# MCU_STM32H750VBT6.net
KiCad netlist of a schematic drawn in Altium Designer
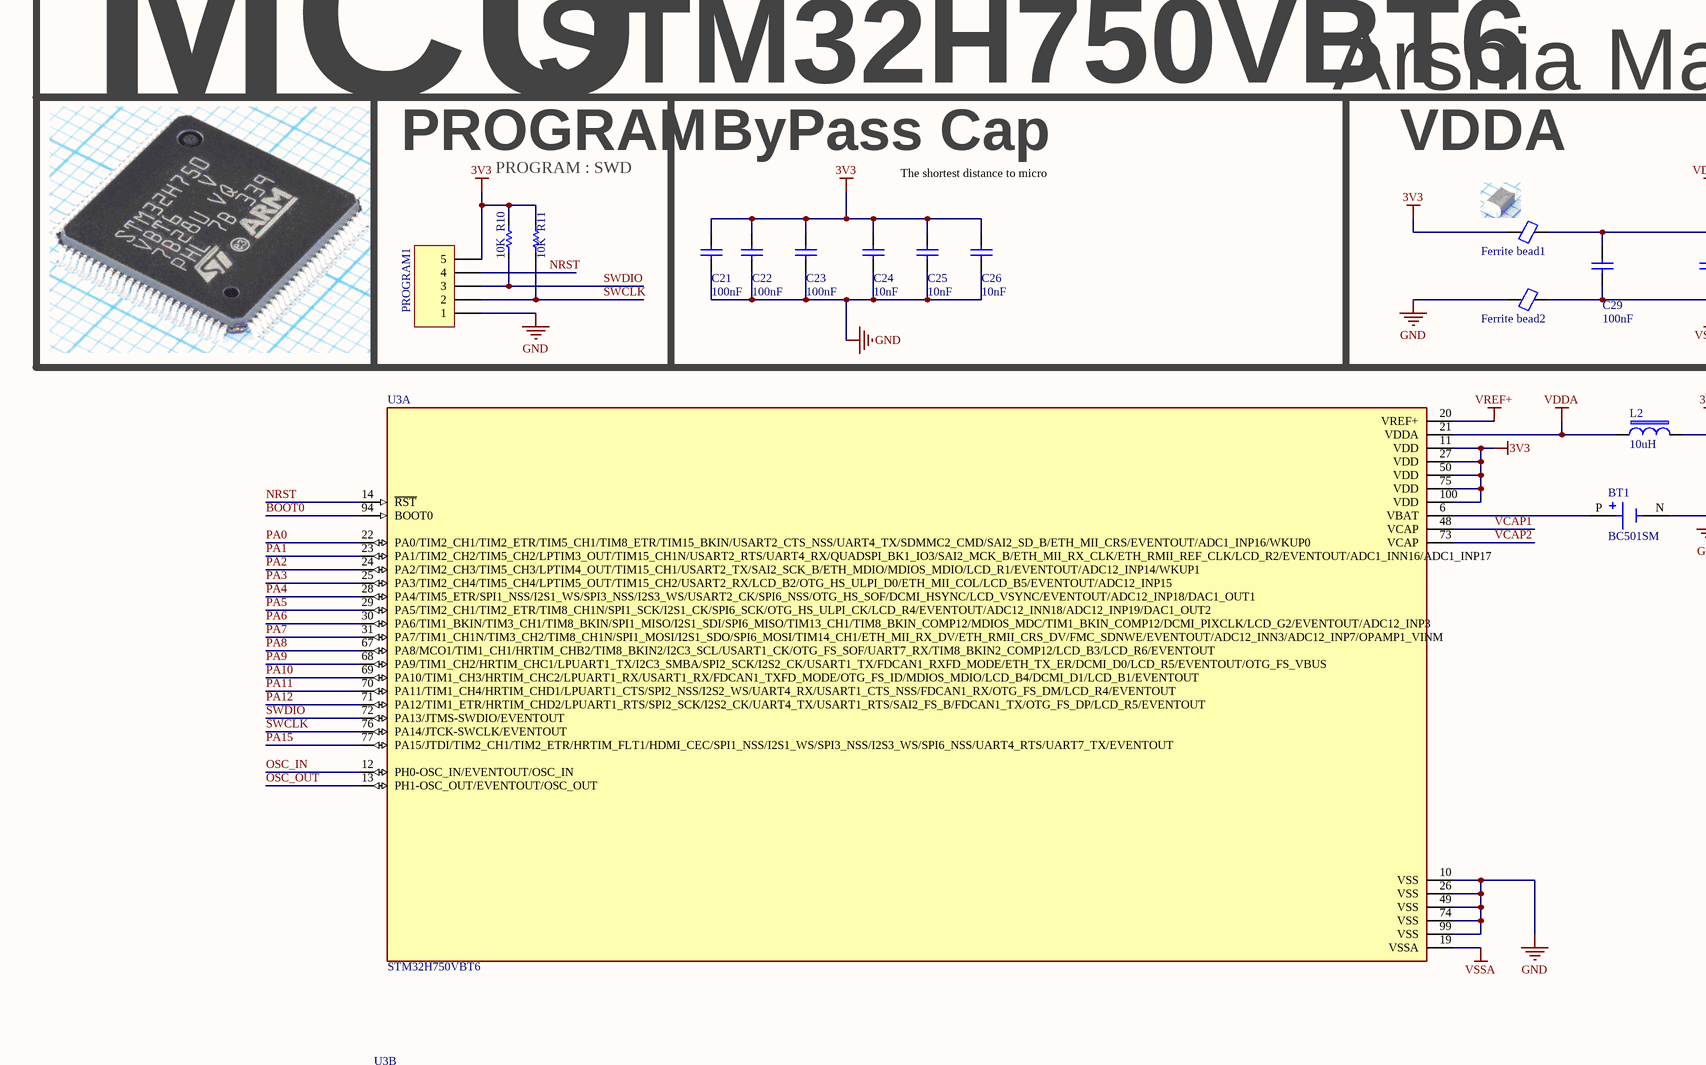
[diagram p0: MCU_STM32H750VBT6.SchDoc, top left]
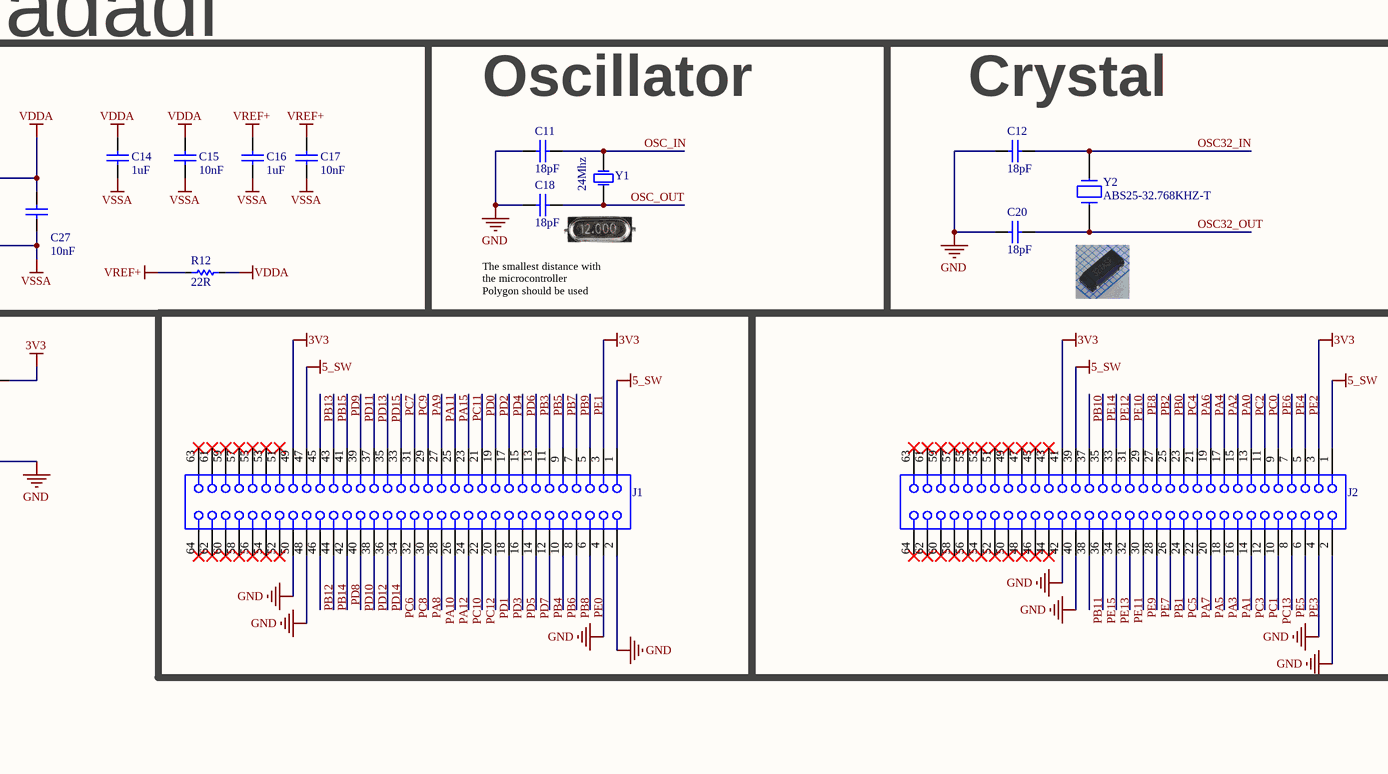
[diagram p1: MCU_STM32H750VBT6.SchDoc, top middle]
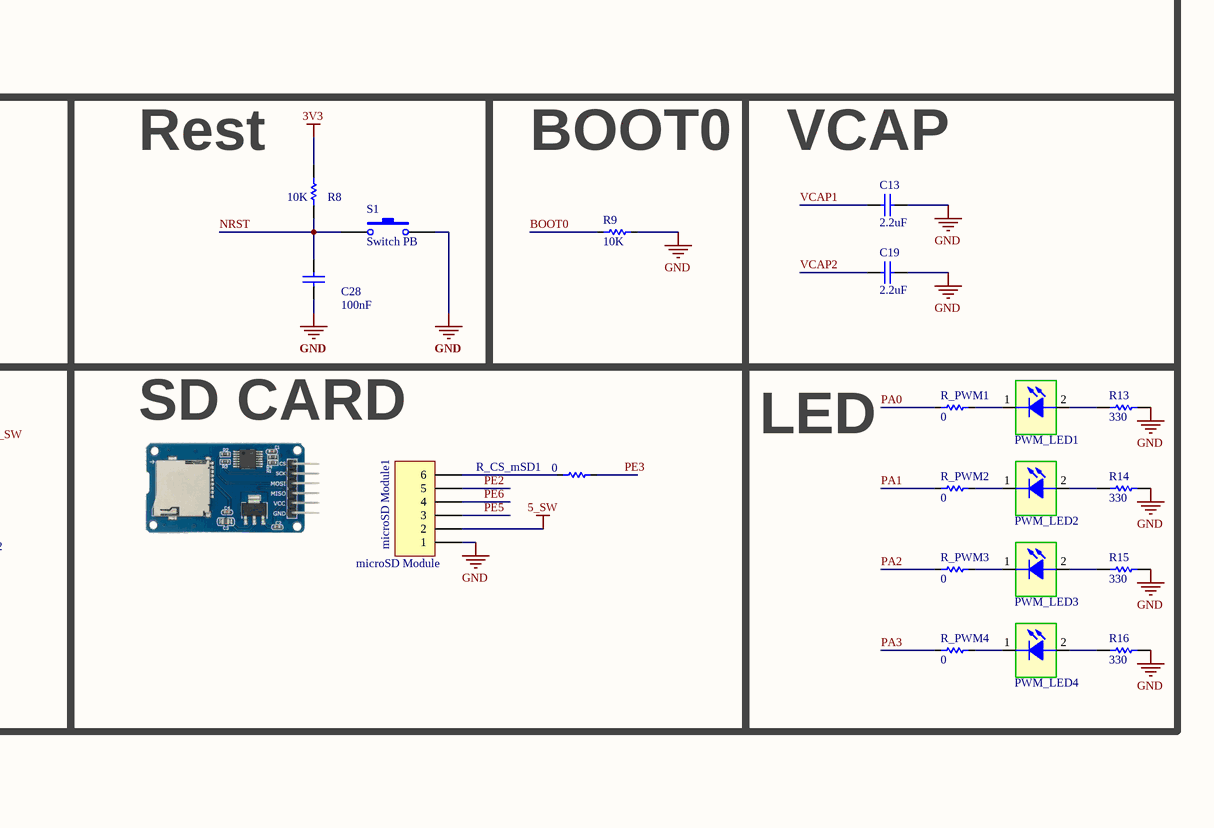
[diagram p2: MCU_STM32H750VBT6.SchDoc, top right]
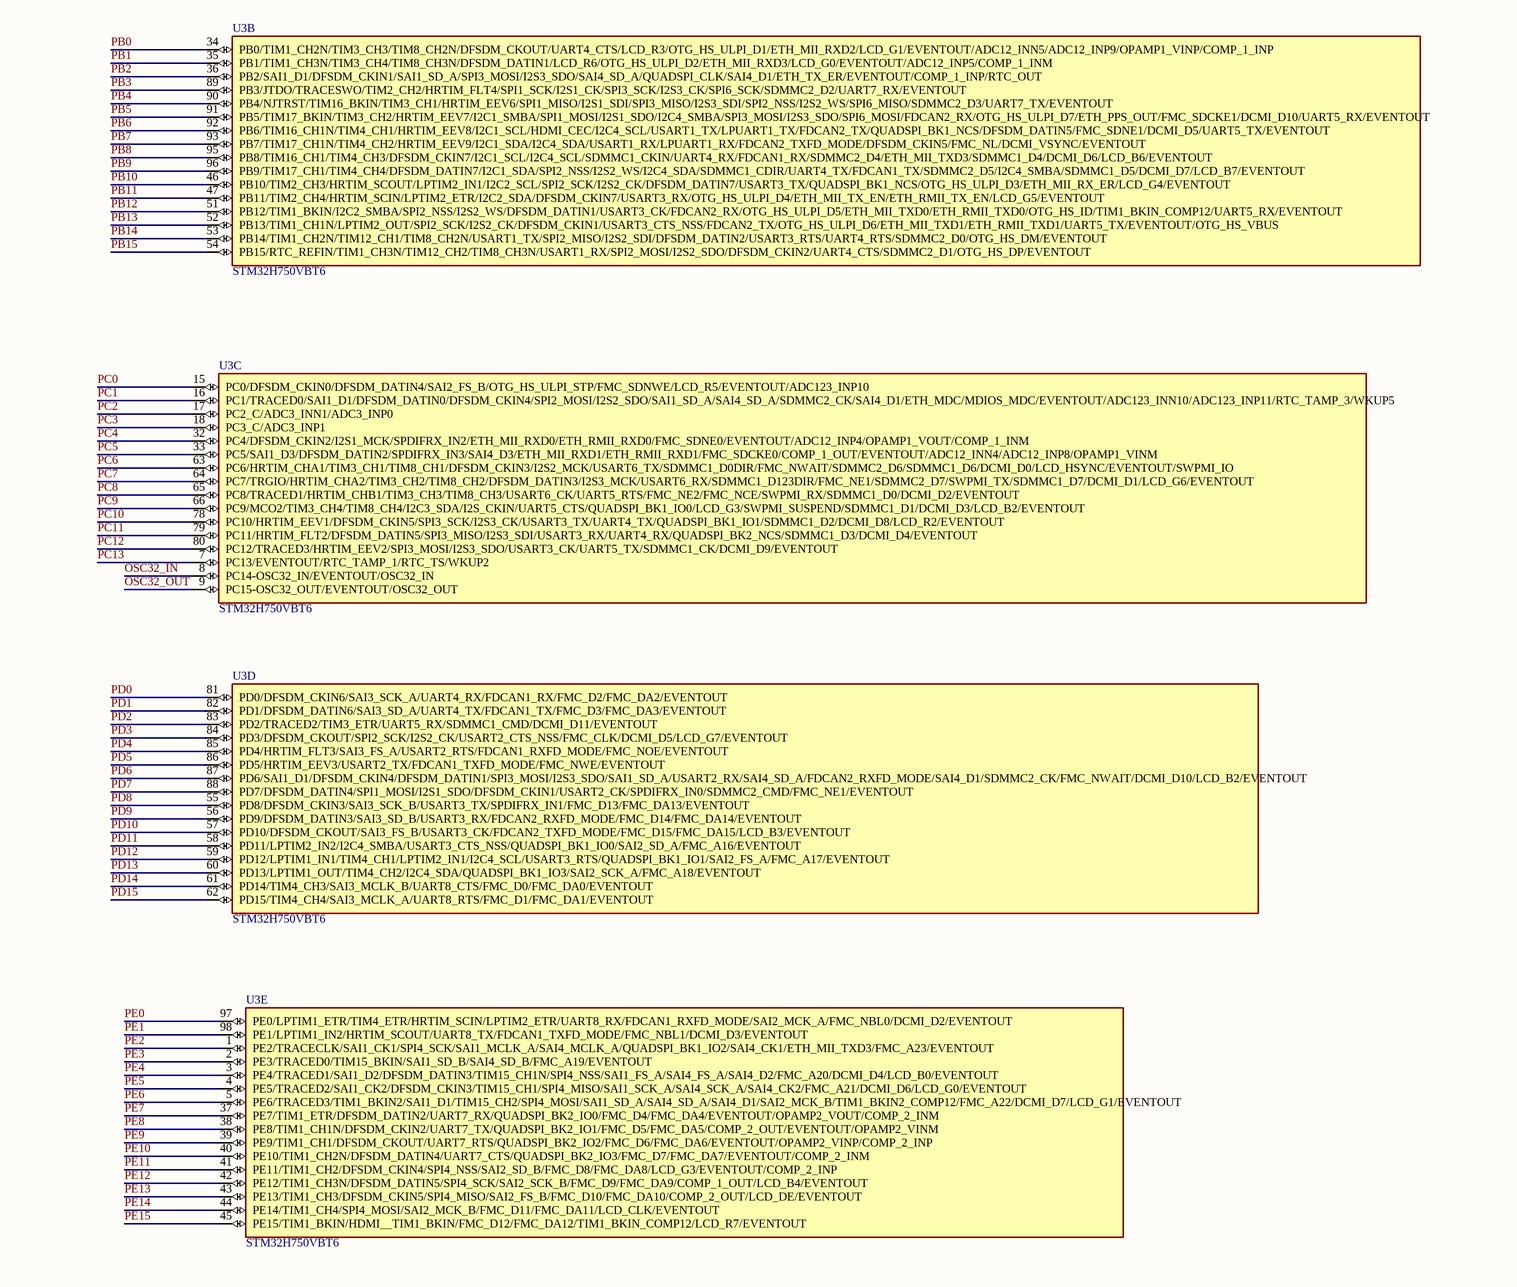
[diagram p3: MCU_STM32H750VBT6.SchDoc, bottom left]

(export (version "E")
  (design (tool "Eeschema 10.0.6"))
  (components
    (comp (ref "BT1")
      (value "BC501SM")
      (footprint "BAT_BC501SM")
      (description "BATTERY HOLDER COIN 12MM SMD")
      (fields (field (name "MF") "MPD"))
      (libsource (lib "BC501SM") (part "BC501SM"))
    )
    (comp (ref "C11")
      (value "18pF")
      (footprint "MY_CAP_SMD_0603")
      (description "CAP SMD_0603")
      (libsource (lib "AMINLIB") (part "CAP SMD_0603"))
    )
    (comp (ref "C12")
      (value "18pF")
      (footprint "MY_CAP_SMD_0603")
      (description "CAP SMD_0603")
      (libsource (lib "AMINLIB") (part "CAP SMD_0603"))
    )
    (comp (ref "C13")
      (value "2.2uF")
      (footprint "MY_CAP_SMD_0603")
      (description "CAP SMD_0603")
      (libsource (lib "AMINLIB") (part "CAP SMD_0603"))
    )
    (comp (ref "C14")
      (value "1uF")
      (footprint "MY_CAP_SMD_0603")
      (description "CAP SMD_0603")
      (libsource (lib "AMINLIB") (part "CAP SMD_0603"))
    )
    (comp (ref "C15")
      (value "10nF")
      (footprint "MY_CAP_SMD_0603")
      (description "CAP SMD_0603")
      (libsource (lib "AMINLIB") (part "CAP SMD_0603"))
    )
    (comp (ref "C16")
      (value "1uF")
      (footprint "MY_CAP_SMD_0603")
      (description "CAP SMD_0603")
      (libsource (lib "AMINLIB") (part "CAP SMD_0603"))
    )
    (comp (ref "C17")
      (value "10nF")
      (footprint "MY_CAP_SMD_0603")
      (description "CAP SMD_0603")
      (libsource (lib "AMINLIB") (part "CAP SMD_0603"))
    )
    (comp (ref "C18")
      (value "18pF")
      (footprint "MY_CAP_SMD_0603")
      (description "CAP SMD_0603")
      (libsource (lib "AMINLIB") (part "CAP SMD_0603"))
    )
    (comp (ref "C19")
      (value "2.2uF")
      (footprint "MY_CAP_SMD_0603")
      (description "CAP SMD_0603")
      (libsource (lib "AMINLIB") (part "CAP SMD_0603"))
    )
    (comp (ref "C20")
      (value "18pF")
      (footprint "MY_CAP_SMD_0603")
      (description "CAP SMD_0603")
      (libsource (lib "AMINLIB") (part "CAP SMD_0603"))
    )
    (comp (ref "C21")
      (value "100nF")
      (footprint "MY_CAP_SMD_0603")
      (description "CAP SMD_0603")
      (libsource (lib "AMINLIB") (part "CAP SMD_0603"))
    )
    (comp (ref "C22")
      (value "100nF")
      (footprint "MY_CAP_SMD_0603")
      (description "CAP SMD_0603")
      (libsource (lib "AMINLIB") (part "CAP SMD_0603"))
    )
    (comp (ref "C23")
      (value "100nF")
      (footprint "MY_CAP_SMD_0603")
      (description "CAP SMD_0603")
      (libsource (lib "AMINLIB") (part "CAP SMD_0603"))
    )
    (comp (ref "C24")
      (value "10nF")
      (footprint "MY_CAP_SMD_0603")
      (description "CAP SMD_0603")
      (libsource (lib "AMINLIB") (part "CAP SMD_0603"))
    )
    (comp (ref "C25")
      (value "10nF")
      (footprint "MY_CAP_SMD_0603")
      (description "CAP SMD_0603")
      (libsource (lib "AMINLIB") (part "CAP SMD_0603"))
    )
    (comp (ref "C26")
      (value "10nF")
      (footprint "MY_CAP_SMD_0603")
      (description "CAP SMD_0603")
      (libsource (lib "AMINLIB") (part "CAP SMD_0603"))
    )
    (comp (ref "C27")
      (value "10nF")
      (footprint "MY_CAP_SMD_0603")
      (description "CAP SMD_0603")
      (libsource (lib "AMINLIB") (part "CAP SMD_0603"))
    )
    (comp (ref "C28")
      (value "100nF")
      (footprint "MY_CAP_SMD_0603")
      (description "CAP SMD_0603")
      (libsource (lib "AMINLIB") (part "CAP SMD_0603"))
    )
    (comp (ref "C29")
      (value "100nF")
      (footprint "MY_CAP_SMD_0603")
      (description "CAP SMD_0603")
      (libsource (lib "AMINLIB") (part "CAP SMD_0603"))
    )
    (comp (ref "Ferrite bead1")
      (value "Ferrite Bead SMD")
      (footprint "FB1206")
      (fields (field (name "DESIGNER") "Ali Hafizi"))
      (libsource (lib "Altium") (part "Ferrite Bead SMD Package"))
    )
    (comp (ref "Ferrite bead2")
      (value "Ferrite Bead SMD")
      (footprint "FB1206")
      (fields (field (name "DESIGNER") "Ali Hafizi"))
      (libsource (lib "Altium") (part "Ferrite Bead SMD Package"))
    )
    (comp (ref "J1")
      (value "61306421821")
      (footprint "61306421821")
      (description "WR-PHD Socket Header, THT, Vertical, pitch 2.54mm, 2 Row, 64P")
      (fields (field (name "MANUFACTURER") "Wurth Elektronik"))
      (libsource (lib "Altium_WR-PHD_rev24a") (part "61306421821"))
    )
    (comp (ref "J2")
      (value "61306421821")
      (footprint "61306421821")
      (description "WR-PHD Socket Header, THT, Vertical, pitch 2.54mm, 2 Row, 64P")
      (fields (field (name "MANUFACTURER") "Wurth Elektronik"))
      (libsource (lib "Altium_WR-PHD_rev24a") (part "61306421821"))
    )
    (comp (ref "L2")
      (value "10uH")
      (footprint "10UH")
      (description "Inductor")
      (fields (field (name "PUBLISHER") "Altium Limited"))
      (libsource (lib "Sajad_Altium_Library") (part "Inductor_B"))
    )
    (comp (ref "microSD Module1")
      (value "microSD Module")
      (footprint "HDR1X6-1")
      (description "Header, 6-Pin")
      (fields (field (name "PUBLISHER") "Altium Limited"))
      (libsource (lib "Altium") (part "Header 6"))
    )
    (comp (ref "PROGRAM1")
      (value "Header 5")
      (footprint "My_1X05")
      (description "Header, 5-Pin")
      (fields (field (name "PUBLISHER") "Altium Limited"))
      (libsource (lib "AMINLIB") (part "Header 5"))
    )
    (comp (ref "PWM_LED1")
      (value "SMD 1206 LED")
      (footprint "LED 1206")
      (libsource (lib "Altium") (part "LED SMD 1206"))
    )
    (comp (ref "PWM_LED2")
      (value "SMD 1206 LED")
      (footprint "LED 1206")
      (libsource (lib "Altium") (part "LED SMD 1206"))
    )
    (comp (ref "PWM_LED3")
      (value "SMD 1206 LED")
      (footprint "LED 1206")
      (libsource (lib "Altium") (part "LED SMD 1206"))
    )
    (comp (ref "PWM_LED4")
      (value "SMD 1206 LED")
      (footprint "LED 1206")
      (libsource (lib "Altium") (part "LED SMD 1206"))
    )
    (comp (ref "R8")
      (value "10K")
      (footprint "RESC4817X04N")
      (description "RES 1206")
      (fields (field (name "DESIGNER") "Abbas Basereh"))
      (libsource (lib "Altium") (part "RES 1206 0.25W"))
    )
    (comp (ref "R9")
      (value "10K")
      (footprint "0805")
      (description "Resistor")
      (fields (field (name "PUBLISHER") "Altium Limited"))
      (libsource (lib "Sajad_Altium_Library") (part "Res"))
    )
    (comp (ref "R10")
      (value "10K")
      (footprint "0805")
      (description "Resistor")
      (fields (field (name "PUBLISHER") "Altium Limited"))
      (libsource (lib "Sajad_Altium_Library") (part "Res"))
    )
    (comp (ref "R11")
      (value "10K")
      (footprint "0805")
      (description "Resistor")
      (fields (field (name "PUBLISHER") "Altium Limited"))
      (libsource (lib "Sajad_Altium_Library") (part "Res"))
    )
    (comp (ref "R12")
      (value "22R")
      (footprint "0805")
      (description "Resistor")
      (fields (field (name "PUBLISHER") "Altium Limited"))
      (libsource (lib "Sajad_Altium_Library") (part "Res"))
    )
    (comp (ref "R13")
      (value "330")
      (footprint "RESC3413X04N")
      (description "RES 0805")
      (fields (field (name "DESIGNER") "Abbas Basereh"))
      (libsource (lib "Altium") (part "RES 0805 0.125W"))
    )
    (comp (ref "R14")
      (value "330")
      (footprint "RESC3413X04N")
      (description "RES 0805")
      (fields (field (name "DESIGNER") "Abbas Basereh"))
      (libsource (lib "Altium") (part "RES 0805 0.125W"))
    )
    (comp (ref "R15")
      (value "330")
      (footprint "RESC3413X04N")
      (description "RES 0805")
      (fields (field (name "DESIGNER") "Abbas Basereh"))
      (libsource (lib "Altium") (part "RES 0805 0.125W"))
    )
    (comp (ref "R16")
      (value "330")
      (footprint "RESC3413X04N")
      (description "RES 0805")
      (fields (field (name "DESIGNER") "Abbas Basereh"))
      (libsource (lib "Altium") (part "RES 0805 0.125W"))
    )
    (comp (ref "R_CS_mSD1")
      (value "0")
      (footprint "0805")
      (description "Resistor")
      (fields (field (name "PUBLISHER") "Altium Limited"))
      (libsource (lib "Sajad_Altium_Library") (part "Res"))
    )
    (comp (ref "R_PWM1")
      (value "0")
      (footprint "0805")
      (description "Resistor")
      (fields (field (name "PUBLISHER") "Altium Limited"))
      (libsource (lib "Sajad_Altium_Library") (part "Res"))
    )
    (comp (ref "R_PWM2")
      (value "0")
      (footprint "0805")
      (description "Resistor")
      (fields (field (name "PUBLISHER") "Altium Limited"))
      (libsource (lib "Sajad_Altium_Library") (part "Res"))
    )
    (comp (ref "R_PWM3")
      (value "0")
      (footprint "0805")
      (description "Resistor")
      (fields (field (name "PUBLISHER") "Altium Limited"))
      (libsource (lib "Sajad_Altium_Library") (part "Res"))
    )
    (comp (ref "R_PWM4")
      (value "0")
      (footprint "0805")
      (description "Resistor")
      (fields (field (name "PUBLISHER") "Altium Limited"))
      (libsource (lib "Sajad_Altium_Library") (part "Res"))
    )
    (comp (ref "S1")
      (value "Switch PB")
      (footprint "SW-PB")
      (description "Push Button Switch")
      (libsource (lib "my library") (part "Switch PB"))
    )
    (comp (ref "U3")
      (value "STM32H750VBT6")
      (footprint "QFP50P1600X1600X160-100N")
      (fields (field (name "MF") "STMicroelectronics"))
      (libsource (lib "STM32H750VBT6") (part "STM32H750VBT6"))
    )
    (comp (ref "Y1")
      (value "24Mhz")
      (footprint "Crystal")
      (description "Crystal Oscillator")
      (fields (field (name "PUBLISHER") "Altium Limited"))
      (libsource (lib "Sajad_Altium_Library") (part "XTAL"))
    )
    (comp (ref "Y2")
      (value "ABS25-32.768KHZ-T")
      (footprint "MY_CRYSTAL_SMD 6 X 3.3")
      (description "Crystal")
      (libsource (lib "AMINLIB") (part "CRYSTAL_SMD-6X3.3"))
    )
  )
  (nets
    (net (code "1") (name "/BOOT0") (class "Default")
      (node (ref "R9") (pin "1") (pinfunction "1_1") (pintype "passive"))
      (node (ref "U3") (pin "94") (pinfunction "BOOT0_94") (pintype "input"))
    )
    (net (code "2") (name "/NRST") (class "Default")
      (node (ref "C28") (pin "1") (pinfunction "1_1") (pintype "passive"))
      (node (ref "PROGRAM1") (pin "4") (pinfunction "4_4") (pintype "passive"))
      (node (ref "R8") (pin "1") (pinfunction "1_1") (pintype "passive"))
      (node (ref "S1") (pin "1") (pinfunction "1_1") (pintype "passive"))
      (node (ref "U3") (pin "14") (pinfunction "~{RST}_14") (pintype "input"))
    )
    (net (code "3") (name "/OSC32_IN") (class "Default")
      (node (ref "C12") (pin "2") (pinfunction "2_2") (pintype "passive"))
      (node (ref "U3") (pin "8") (pinfunction "PC14-OSC32_IN/EVENTOUT/OSC32_IN_8") (pintype "bidirectional"))
      (node (ref "Y2") (pin "4") (pinfunction "3_4") (pintype "passive"))
    )
    (net (code "4") (name "/OSC32_OUT") (class "Default")
      (node (ref "C20") (pin "2") (pinfunction "2_2") (pintype "passive"))
      (node (ref "U3") (pin "9") (pinfunction "PC15-OSC32_OUT/EVENTOUT/OSC32_OUT_9") (pintype "bidirectional"))
      (node (ref "Y2") (pin "2") (pinfunction "1_2") (pintype "passive"))
    )
    (net (code "5") (name "/OSC_IN") (class "Default")
      (node (ref "C11") (pin "2") (pinfunction "2_2") (pintype "passive"))
      (node (ref "U3") (pin "12") (pinfunction "PH0-OSC_IN/EVENTOUT/OSC_IN_12") (pintype "bidirectional"))
      (node (ref "Y1") (pin "2") (pinfunction "OSC2_2") (pintype "passive"))
    )
    (net (code "6") (name "/OSC_OUT") (class "Default")
      (node (ref "C18") (pin "2") (pinfunction "2_2") (pintype "passive"))
      (node (ref "U3") (pin "13") (pinfunction "PH1-OSC_OUT/EVENTOUT/OSC_OUT_13") (pintype "bidirectional"))
      (node (ref "Y1") (pin "1") (pinfunction "OSC1_1") (pintype "passive"))
    )
    (net (code "7") (name "/PA0") (class "Default")
      (node (ref "J2") (pin "15") (pinfunction "15_15") (pintype "passive"))
      (node (ref "R_PWM1") (pin "1") (pinfunction "1_1") (pintype "passive"))
      (node (ref "U3") (pin "22") (pinfunction "PA0/TIM2_CH1/TIM2_ETR/TIM5_CH1/TIM8_ETR/TIM15_BKIN/USART2_CTS_NSS/UART4_TX/SDMMC2_CMD/SAI2_SD_B/ETH_MII_CRS/EVENTOUT/ADC1_INP16/WKUP0_22") (pintype "bidirectional"))
    )
    (net (code "8") (name "/PA1") (class "Default")
      (node (ref "J2") (pin "16") (pinfunction "16_16") (pintype "passive"))
      (node (ref "R_PWM2") (pin "1") (pinfunction "1_1") (pintype "passive"))
      (node (ref "U3") (pin "23") (pinfunction "PA1/TIM2_CH2/TIM5_CH2/LPTIM3_OUT/TIM15_CH1N/USART2_RTS/UART4_RX/QUADSPI_BK1_IO3/SAI2_MCK_B/ETH_MII_RX_CLK/ETH_RMII_REF_CLK/LCD_R2/EVENTOUT/ADC1_INN16/ADC1_INP17_23") (pintype "bidirectional"))
    )
    (net (code "9") (name "/PA2") (class "Default")
      (node (ref "J2") (pin "17") (pinfunction "17_17") (pintype "passive"))
      (node (ref "R_PWM3") (pin "1") (pinfunction "1_1") (pintype "passive"))
      (node (ref "U3") (pin "24") (pinfunction "PA2/TIM2_CH3/TIM5_CH3/LPTIM4_OUT/TIM15_CH1/USART2_TX/SAI2_SCK_B/ETH_MDIO/MDIOS_MDIO/LCD_R1/EVENTOUT/ADC12_INP14/WKUP1_24") (pintype "bidirectional"))
    )
    (net (code "10") (name "/PA3") (class "Default")
      (node (ref "J2") (pin "18") (pinfunction "18_18") (pintype "passive"))
      (node (ref "R_PWM4") (pin "1") (pinfunction "1_1") (pintype "passive"))
      (node (ref "U3") (pin "25") (pinfunction "PA3/TIM2_CH4/TIM5_CH4/LPTIM5_OUT/TIM15_CH2/USART2_RX/LCD_B2/OTG_HS_ULPI_D0/ETH_MII_COL/LCD_B5/EVENTOUT/ADC12_INP15_25") (pintype "bidirectional"))
    )
    (net (code "11") (name "/PA4") (class "Default")
      (node (ref "J2") (pin "19") (pinfunction "19_19") (pintype "passive"))
      (node (ref "U3") (pin "28") (pinfunction "PA4/TIM5_ETR/SPI1_NSS/I2S1_WS/SPI3_NSS/I2S3_WS/USART2_CK/SPI6_NSS/OTG_HS_SOF/DCMI_HSYNC/LCD_VSYNC/EVENTOUT/ADC12_INP18/DAC1_OUT1_28") (pintype "bidirectional"))
    )
    (net (code "12") (name "/PA5") (class "Default")
      (node (ref "J2") (pin "20") (pinfunction "20_20") (pintype "passive"))
      (node (ref "U3") (pin "29") (pinfunction "PA5/TIM2_CH1/TIM2_ETR/TIM8_CH1N/SPI1_SCK/I2S1_CK/SPI6_SCK/OTG_HS_ULPI_CK/LCD_R4/EVENTOUT/ADC12_INN18/ADC12_INP19/DAC1_OUT2_29") (pintype "bidirectional"))
    )
    (net (code "13") (name "/PA6") (class "Default")
      (node (ref "J2") (pin "21") (pinfunction "21_21") (pintype "passive"))
      (node (ref "U3") (pin "30") (pinfunction "PA6/TIM1_BKIN/TIM3_CH1/TIM8_BKIN/SPI1_MISO/I2S1_SDI/SPI6_MISO/TIM13_CH1/TIM8_BKIN_COMP12/MDIOS_MDC/TIM1_BKIN_COMP12/DCMI_PIXCLK/LCD_G2/EVENTOUT/ADC12_INP3_30") (pintype "bidirectional"))
    )
    (net (code "14") (name "/PA7") (class "Default")
      (node (ref "J2") (pin "22") (pinfunction "22_22") (pintype "passive"))
      (node (ref "U3") (pin "31") (pinfunction "PA7/TIM1_CH1N/TIM3_CH2/TIM8_CH1N/SPI1_MOSI/I2S1_SDO/SPI6_MOSI/TIM14_CH1/ETH_MII_RX_DV/ETH_RMII_CRS_DV/FMC_SDNWE/EVENTOUT/ADC12_INN3/ADC12_INP7/OPAMP1_VINM_31") (pintype "bidirectional"))
    )
    (net (code "15") (name "/PA8") (class "Default")
      (node (ref "J1") (pin "30") (pinfunction "30_30") (pintype "passive"))
      (node (ref "U3") (pin "67") (pinfunction "PA8/MCO1/TIM1_CH1/HRTIM_CHB2/TIM8_BKIN2/I2C3_SCL/USART1_CK/OTG_FS_SOF/UART7_RX/TIM8_BKIN2_COMP12/LCD_B3/LCD_R6/EVENTOUT_67") (pintype "bidirectional"))
    )
    (net (code "16") (name "/PA9") (class "Default")
      (node (ref "J1") (pin "29") (pinfunction "29_29") (pintype "passive"))
      (node (ref "U3") (pin "68") (pinfunction "PA9/TIM1_CH2/HRTIM_CHC1/LPUART1_TX/I2C3_SMBA/SPI2_SCK/I2S2_CK/USART1_TX/FDCAN1_RXFD_MODE/ETH_TX_ER/DCMI_D0/LCD_R5/EVENTOUT/OTG_FS_VBUS_68") (pintype "bidirectional"))
    )
    (net (code "17") (name "/PA10") (class "Default")
      (node (ref "J1") (pin "28") (pinfunction "28_28") (pintype "passive"))
      (node (ref "U3") (pin "69") (pinfunction "PA10/TIM1_CH3/HRTIM_CHC2/LPUART1_RX/USART1_RX/FDCAN1_TXFD_MODE/OTG_FS_ID/MDIOS_MDIO/LCD_B4/DCMI_D1/LCD_B1/EVENTOUT_69") (pintype "bidirectional"))
    )
    (net (code "18") (name "/PA11") (class "Default")
      (node (ref "J1") (pin "27") (pinfunction "27_27") (pintype "passive"))
      (node (ref "U3") (pin "70") (pinfunction "PA11/TIM1_CH4/HRTIM_CHD1/LPUART1_CTS/SPI2_NSS/I2S2_WS/UART4_RX/USART1_CTS_NSS/FDCAN1_RX/OTG_FS_DM/LCD_R4/EVENTOUT_70") (pintype "bidirectional"))
    )
    (net (code "19") (name "/PA12") (class "Default")
      (node (ref "J1") (pin "26") (pinfunction "26_26") (pintype "passive"))
      (node (ref "U3") (pin "71") (pinfunction "PA12/TIM1_ETR/HRTIM_CHD2/LPUART1_RTS/SPI2_SCK/I2S2_CK/UART4_TX/USART1_RTS/SAI2_FS_B/FDCAN1_TX/OTG_FS_DP/LCD_R5/EVENTOUT_71") (pintype "bidirectional"))
    )
    (net (code "20") (name "/PA15") (class "Default")
      (node (ref "J1") (pin "25") (pinfunction "25_25") (pintype "passive"))
      (node (ref "U3") (pin "77") (pinfunction "PA15/JTDI/TIM2_CH1/TIM2_ETR/HRTIM_FLT1/HDMI_CEC/SPI1_NSS/I2S1_WS/SPI3_NSS/I2S3_WS/SPI6_NSS/UART4_RTS/UART7_TX/EVENTOUT_77") (pintype "bidirectional"))
    )
    (net (code "21") (name "/PB0") (class "Default")
      (node (ref "J2") (pin "25") (pinfunction "25_25") (pintype "passive"))
      (node (ref "U3") (pin "34") (pinfunction "PB0/TIM1_CH2N/TIM3_CH3/TIM8_CH2N/DFSDM_CKOUT/UART4_CTS/LCD_R3/OTG_HS_ULPI_D1/ETH_MII_RXD2/LCD_G1/EVENTOUT/ADC12_INN5/ADC12_INP9/OPAMP1_VINP/COMP_1_INP_34") (pintype "bidirectional"))
    )
    (net (code "22") (name "/PB1") (class "Default")
      (node (ref "J2") (pin "26") (pinfunction "26_26") (pintype "passive"))
      (node (ref "U3") (pin "35") (pinfunction "PB1/TIM1_CH3N/TIM3_CH4/TIM8_CH3N/DFSDM_DATIN1/LCD_R6/OTG_HS_ULPI_D2/ETH_MII_RXD3/LCD_G0/EVENTOUT/ADC12_INP5/COMP_1_INM_35") (pintype "bidirectional"))
    )
    (net (code "23") (name "/PB2") (class "Default")
      (node (ref "J2") (pin "27") (pinfunction "27_27") (pintype "passive"))
      (node (ref "U3") (pin "36") (pinfunction "PB2/SAI1_D1/DFSDM_CKIN1/SAI1_SD_A/SPI3_MOSI/I2S3_SDO/SAI4_SD_A/QUADSPI_CLK/SAI4_D1/ETH_TX_ER/EVENTOUT/COMP_1_INP/RTC_OUT_36") (pintype "bidirectional"))
    )
    (net (code "24") (name "/PB3") (class "Default")
      (node (ref "J1") (pin "13") (pinfunction "13_13") (pintype "passive"))
      (node (ref "U3") (pin "89") (pinfunction "PB3/JTDO/TRACESWO/TIM2_CH2/HRTIM_FLT4/SPI1_SCK/I2S1_CK/SPI3_SCK/I2S3_CK/SPI6_SCK/SDMMC2_D2/UART7_RX/EVENTOUT_89") (pintype "bidirectional"))
    )
    (net (code "25") (name "/PB4") (class "Default")
      (node (ref "J1") (pin "12") (pinfunction "12_12") (pintype "passive"))
      (node (ref "U3") (pin "90") (pinfunction "PB4/NJTRST/TIM16_BKIN/TIM3_CH1/HRTIM_EEV6/SPI1_MISO/I2S1_SDI/SPI3_MISO/I2S3_SDI/SPI2_NSS/I2S2_WS/SPI6_MISO/SDMMC2_D3/UART7_TX/EVENTOUT_90") (pintype "bidirectional"))
    )
    (net (code "26") (name "/PB5") (class "Default")
      (node (ref "J1") (pin "11") (pinfunction "11_11") (pintype "passive"))
      (node (ref "U3") (pin "91") (pinfunction "PB5/TIM17_BKIN/TIM3_CH2/HRTIM_EEV7/I2C1_SMBA/SPI1_MOSI/I2S1_SDO/I2C4_SMBA/SPI3_MOSI/I2S3_SDO/SPI6_MOSI/FDCAN2_RX/OTG_HS_ULPI_D7/ETH_PPS_OUT/FMC_SDCKE1/DCMI_D10/UART5_RX/EVENTOUT_91") (pintype "bidirectional"))
    )
    (net (code "27") (name "/PB6") (class "Default")
      (node (ref "J1") (pin "10") (pinfunction "10_10") (pintype "passive"))
      (node (ref "U3") (pin "92") (pinfunction "PB6/TIM16_CH1N/TIM4_CH1/HRTIM_EEV8/I2C1_SCL/HDMI_CEC/I2C4_SCL/USART1_TX/LPUART1_TX/FDCAN2_TX/QUADSPI_BK1_NCS/DFSDM_DATIN5/FMC_SDNE1/DCMI_D5/UART5_TX/EVENTOUT_92") (pintype "bidirectional"))
    )
    (net (code "28") (name "/PB7") (class "Default")
      (node (ref "J1") (pin "9") (pinfunction "9_9") (pintype "passive"))
      (node (ref "U3") (pin "93") (pinfunction "PB7/TIM17_CH1N/TIM4_CH2/HRTIM_EEV9/I2C1_SDA/I2C4_SDA/USART1_RX/LPUART1_RX/FDCAN2_TXFD_MODE/DFSDM_CKIN5/FMC_NL/DCMI_VSYNC/EVENTOUT_93") (pintype "bidirectional"))
    )
    (net (code "29") (name "/PB8") (class "Default")
      (node (ref "J1") (pin "8") (pinfunction "8_8") (pintype "passive"))
      (node (ref "U3") (pin "95") (pinfunction "PB8/TIM16_CH1/TIM4_CH3/DFSDM_CKIN7/I2C1_SCL/I2C4_SCL/SDMMC1_CKIN/UART4_RX/FDCAN1_RX/SDMMC2_D4/ETH_MII_TXD3/SDMMC1_D4/DCMI_D6/LCD_B6/EVENTOUT_95") (pintype "bidirectional"))
    )
    (net (code "30") (name "/PB9") (class "Default")
      (node (ref "J1") (pin "7") (pinfunction "7_7") (pintype "passive"))
      (node (ref "U3") (pin "96") (pinfunction "PB9/TIM17_CH1/TIM4_CH4/DFSDM_DATIN7/I2C1_SDA/SPI2_NSS/I2S2_WS/I2C4_SDA/SDMMC1_CDIR/UART4_TX/FDCAN1_TX/SDMMC2_D5/I2C4_SMBA/SDMMC1_D5/DCMI_D7/LCD_B7/EVENTOUT_96") (pintype "bidirectional"))
    )
    (net (code "31") (name "/PB10") (class "Default")
      (node (ref "J2") (pin "37") (pinfunction "37_37") (pintype "passive"))
      (node (ref "U3") (pin "46") (pinfunction "PB10/TIM2_CH3/HRTIM_SCOUT/LPTIM2_IN1/I2C2_SCL/SPI2_SCK/I2S2_CK/DFSDM_DATIN7/USART3_TX/QUADSPI_BK1_NCS/OTG_HS_ULPI_D3/ETH_MII_RX_ER/LCD_G4/EVENTOUT_46") (pintype "bidirectional"))
    )
    (net (code "32") (name "/PB11") (class "Default")
      (node (ref "J2") (pin "38") (pinfunction "38_38") (pintype "passive"))
      (node (ref "U3") (pin "47") (pinfunction "PB11/TIM2_CH4/HRTIM_SCIN/LPTIM2_ETR/I2C2_SDA/DFSDM_CKIN7/USART3_RX/OTG_HS_ULPI_D4/ETH_MII_TX_EN/ETH_RMII_TX_EN/LCD_G5/EVENTOUT_47") (pintype "bidirectional"))
    )
    (net (code "33") (name "/PB12") (class "Default")
      (node (ref "J1") (pin "46") (pinfunction "46_46") (pintype "passive"))
      (node (ref "U3") (pin "51") (pinfunction "PB12/TIM1_BKIN/I2C2_SMBA/SPI2_NSS/I2S2_WS/DFSDM_DATIN1/USART3_CK/FDCAN2_RX/OTG_HS_ULPI_D5/ETH_MII_TXD0/ETH_RMII_TXD0/OTG_HS_ID/TIM1_BKIN_COMP12/UART5_RX/EVENTOUT_51") (pintype "bidirectional"))
    )
    (net (code "34") (name "/PB13") (class "Default")
      (node (ref "J1") (pin "45") (pinfunction "45_45") (pintype "passive"))
      (node (ref "U3") (pin "52") (pinfunction "PB13/TIM1_CH1N/LPTIM2_OUT/SPI2_SCK/I2S2_CK/DFSDM_CKIN1/USART3_CTS_NSS/FDCAN2_TX/OTG_HS_ULPI_D6/ETH_MII_TXD1/ETH_RMII_TXD1/UART5_TX/EVENTOUT/OTG_HS_VBUS_52") (pintype "bidirectional"))
    )
    (net (code "35") (name "/PB14") (class "Default")
      (node (ref "J1") (pin "44") (pinfunction "44_44") (pintype "passive"))
      (node (ref "U3") (pin "53") (pinfunction "PB14/TIM1_CH2N/TIM12_CH1/TIM8_CH2N/USART1_TX/SPI2_MISO/I2S2_SDI/DFSDM_DATIN2/USART3_RTS/UART4_RTS/SDMMC2_D0/OTG_HS_DM/EVENTOUT_53") (pintype "bidirectional"))
    )
    (net (code "36") (name "/PB15") (class "Default")
      (node (ref "J1") (pin "43") (pinfunction "43_43") (pintype "passive"))
      (node (ref "U3") (pin "54") (pinfunction "PB15/RTC_REFIN/TIM1_CH3N/TIM12_CH2/TIM8_CH3N/USART1_RX/SPI2_MOSI/I2S2_SDO/DFSDM_CKIN2/UART4_CTS/SDMMC2_D1/OTG_HS_DP/EVENTOUT_54") (pintype "bidirectional"))
    )
    (net (code "37") (name "/PC0") (class "Default")
      (node (ref "J2") (pin "11") (pinfunction "11_11") (pintype "passive"))
      (node (ref "U3") (pin "15") (pinfunction "PC0/DFSDM_CKIN0/DFSDM_DATIN4/SAI2_FS_B/OTG_HS_ULPI_STP/FMC_SDNWE/LCD_R5/EVENTOUT/ADC123_INP10_15") (pintype "bidirectional"))
    )
    (net (code "38") (name "/PC1") (class "Default")
      (node (ref "J2") (pin "12") (pinfunction "12_12") (pintype "passive"))
      (node (ref "U3") (pin "16") (pinfunction "PC1/TRACED0/SAI1_D1/DFSDM_DATIN0/DFSDM_CKIN4/SPI2_MOSI/I2S2_SDO/SAI1_SD_A/SAI4_SD_A/SDMMC2_CK/SAI4_D1/ETH_MDC/MDIOS_MDC/EVENTOUT/ADC123_INN10/ADC123_INP11/RTC_TAMP_3/WKUP5_16") (pintype "bidirectional"))
    )
    (net (code "39") (name "/PC2") (class "Default")
      (node (ref "J2") (pin "13") (pinfunction "13_13") (pintype "passive"))
      (node (ref "U3") (pin "17") (pinfunction "PC2_C/ADC3_INN1/ADC3_INP0_17") (pintype "bidirectional"))
    )
    (net (code "40") (name "/PC3") (class "Default")
      (node (ref "J2") (pin "14") (pinfunction "14_14") (pintype "passive"))
      (node (ref "U3") (pin "18") (pinfunction "PC3_C/ADC3_INP1_18") (pintype "bidirectional"))
    )
    (net (code "41") (name "/PC4") (class "Default")
      (node (ref "J2") (pin "23") (pinfunction "23_23") (pintype "passive"))
      (node (ref "U3") (pin "32") (pinfunction "PC4/DFSDM_CKIN2/I2S1_MCK/SPDIFRX_IN2/ETH_MII_RXD0/ETH_RMII_RXD0/FMC_SDNE0/EVENTOUT/ADC12_INP4/OPAMP1_VOUT/COMP_1_INM_32") (pintype "bidirectional"))
    )
    (net (code "42") (name "/PC5") (class "Default")
      (node (ref "J2") (pin "24") (pinfunction "24_24") (pintype "passive"))
      (node (ref "U3") (pin "33") (pinfunction "PC5/SAI1_D3/DFSDM_DATIN2/SPDIFRX_IN3/SAI4_D3/ETH_MII_RXD1/ETH_RMII_RXD1/FMC_SDCKE0/COMP_1_OUT/EVENTOUT/ADC12_INN4/ADC12_INP8/OPAMP1_VINM_33") (pintype "bidirectional"))
    )
    (net (code "43") (name "/PC6") (class "Default")
      (node (ref "J1") (pin "34") (pinfunction "34_34") (pintype "passive"))
      (node (ref "U3") (pin "63") (pinfunction "PC6/HRTIM_CHA1/TIM3_CH1/TIM8_CH1/DFSDM_CKIN3/I2S2_MCK/USART6_TX/SDMMC1_D0DIR/FMC_NWAIT/SDMMC2_D6/SDMMC1_D6/DCMI_D0/LCD_HSYNC/EVENTOUT/SWPMI_IO_63") (pintype "bidirectional"))
    )
    (net (code "44") (name "/PC7") (class "Default")
      (node (ref "J1") (pin "33") (pinfunction "33_33") (pintype "passive"))
      (node (ref "U3") (pin "64") (pinfunction "PC7/TRGIO/HRTIM_CHA2/TIM3_CH2/TIM8_CH2/DFSDM_DATIN3/I2S3_MCK/USART6_RX/SDMMC1_D123DIR/FMC_NE1/SDMMC2_D7/SWPMI_TX/SDMMC1_D7/DCMI_D1/LCD_G6/EVENTOUT_64") (pintype "bidirectional"))
    )
    (net (code "45") (name "/PC8") (class "Default")
      (node (ref "J1") (pin "32") (pinfunction "32_32") (pintype "passive"))
      (node (ref "U3") (pin "65") (pinfunction "PC8/TRACED1/HRTIM_CHB1/TIM3_CH3/TIM8_CH3/USART6_CK/UART5_RTS/FMC_NE2/FMC_NCE/SWPMI_RX/SDMMC1_D0/DCMI_D2/EVENTOUT_65") (pintype "bidirectional"))
    )
    (net (code "46") (name "/PC9") (class "Default")
      (node (ref "J1") (pin "31") (pinfunction "31_31") (pintype "passive"))
      (node (ref "U3") (pin "66") (pinfunction "PC9/MCO2/TIM3_CH4/TIM8_CH4/I2C3_SDA/I2S_CKIN/UART5_CTS/QUADSPI_BK1_IO0/LCD_G3/SWPMI_SUSPEND/SDMMC1_D1/DCMI_D3/LCD_B2/EVENTOUT_66") (pintype "bidirectional"))
    )
    (net (code "47") (name "/PC10") (class "Default")
      (node (ref "J1") (pin "24") (pinfunction "24_24") (pintype "passive"))
      (node (ref "U3") (pin "78") (pinfunction "PC10/HRTIM_EEV1/DFSDM_CKIN5/SPI3_SCK/I2S3_CK/USART3_TX/UART4_TX/QUADSPI_BK1_IO1/SDMMC1_D2/DCMI_D8/LCD_R2/EVENTOUT_78") (pintype "bidirectional"))
    )
    (net (code "48") (name "/PC11") (class "Default")
      (node (ref "J1") (pin "23") (pinfunction "23_23") (pintype "passive"))
      (node (ref "U3") (pin "79") (pinfunction "PC11/HRTIM_FLT2/DFSDM_DATIN5/SPI3_MISO/I2S3_SDI/USART3_RX/UART4_RX/QUADSPI_BK2_NCS/SDMMC1_D3/DCMI_D4/EVENTOUT_79") (pintype "bidirectional"))
    )
    (net (code "49") (name "/PC12") (class "Default")
      (node (ref "J1") (pin "22") (pinfunction "22_22") (pintype "passive"))
      (node (ref "U3") (pin "80") (pinfunction "PC12/TRACED3/HRTIM_EEV2/SPI3_MOSI/I2S3_SDO/USART3_CK/UART5_TX/SDMMC1_CK/DCMI_D9/EVENTOUT_80") (pintype "bidirectional"))
    )
    (net (code "50") (name "/PC13") (class "Default")
      (node (ref "J2") (pin "10") (pinfunction "10_10") (pintype "passive"))
      (node (ref "U3") (pin "7") (pinfunction "PC13/EVENTOUT/RTC_TAMP_1/RTC_TS/WKUP2_7") (pintype "bidirectional"))
    )
    (net (code "51") (name "/PD0") (class "Default")
      (node (ref "J1") (pin "21") (pinfunction "21_21") (pintype "passive"))
      (node (ref "U3") (pin "81") (pinfunction "PD0/DFSDM_CKIN6/SAI3_SCK_A/UART4_RX/FDCAN1_RX/FMC_D2/FMC_DA2/EVENTOUT_81") (pintype "bidirectional"))
    )
    (net (code "52") (name "/PD1") (class "Default")
      (node (ref "J1") (pin "20") (pinfunction "20_20") (pintype "passive"))
      (node (ref "U3") (pin "82") (pinfunction "PD1/DFSDM_DATIN6/SAI3_SD_A/UART4_TX/FDCAN1_TX/FMC_D3/FMC_DA3/EVENTOUT_82") (pintype "bidirectional"))
    )
    (net (code "53") (name "/PD2") (class "Default")
      (node (ref "J1") (pin "19") (pinfunction "19_19") (pintype "passive"))
      (node (ref "U3") (pin "83") (pinfunction "PD2/TRACED2/TIM3_ETR/UART5_RX/SDMMC1_CMD/DCMI_D11/EVENTOUT_83") (pintype "bidirectional"))
    )
    (net (code "54") (name "/PD3") (class "Default")
      (node (ref "J1") (pin "18") (pinfunction "18_18") (pintype "passive"))
      (node (ref "U3") (pin "84") (pinfunction "PD3/DFSDM_CKOUT/SPI2_SCK/I2S2_CK/USART2_CTS_NSS/FMC_CLK/DCMI_D5/LCD_G7/EVENTOUT_84") (pintype "bidirectional"))
    )
    (net (code "55") (name "/PD4") (class "Default")
      (node (ref "J1") (pin "17") (pinfunction "17_17") (pintype "passive"))
      (node (ref "U3") (pin "85") (pinfunction "PD4/HRTIM_FLT3/SAI3_FS_A/USART2_RTS/FDCAN1_RXFD_MODE/FMC_NOE/EVENTOUT_85") (pintype "bidirectional"))
    )
    (net (code "56") (name "/PD5") (class "Default")
      (node (ref "J1") (pin "16") (pinfunction "16_16") (pintype "passive"))
      (node (ref "U3") (pin "86") (pinfunction "PD5/HRTIM_EEV3/USART2_TX/FDCAN1_TXFD_MODE/FMC_NWE/EVENTOUT_86") (pintype "bidirectional"))
    )
    (net (code "57") (name "/PD6") (class "Default")
      (node (ref "J1") (pin "15") (pinfunction "15_15") (pintype "passive"))
      (node (ref "U3") (pin "87") (pinfunction "PD6/SAI1_D1/DFSDM_CKIN4/DFSDM_DATIN1/SPI3_MOSI/I2S3_SDO/SAI1_SD_A/USART2_RX/SAI4_SD_A/FDCAN2_RXFD_MODE/SAI4_D1/SDMMC2_CK/FMC_NWAIT/DCMI_D10/LCD_B2/EVENTOUT_87") (pintype "bidirectional"))
    )
    (net (code "58") (name "/PD7") (class "Default")
      (node (ref "J1") (pin "14") (pinfunction "14_14") (pintype "passive"))
      (node (ref "U3") (pin "88") (pinfunction "PD7/DFSDM_DATIN4/SPI1_MOSI/I2S1_SDO/DFSDM_CKIN1/USART2_CK/SPDIFRX_IN0/SDMMC2_CMD/FMC_NE1/EVENTOUT_88") (pintype "bidirectional"))
    )
    (net (code "59") (name "/PD8") (class "Default")
      (node (ref "J1") (pin "42") (pinfunction "42_42") (pintype "passive"))
      (node (ref "U3") (pin "55") (pinfunction "PD8/DFSDM_CKIN3/SAI3_SCK_B/USART3_TX/SPDIFRX_IN1/FMC_D13/FMC_DA13/EVENTOUT_55") (pintype "bidirectional"))
    )
    (net (code "60") (name "/PD9") (class "Default")
      (node (ref "J1") (pin "41") (pinfunction "41_41") (pintype "passive"))
      (node (ref "U3") (pin "56") (pinfunction "PD9/DFSDM_DATIN3/SAI3_SD_B/USART3_RX/FDCAN2_RXFD_MODE/FMC_D14/FMC_DA14/EVENTOUT_56") (pintype "bidirectional"))
    )
    (net (code "61") (name "/PD10") (class "Default")
      (node (ref "J1") (pin "40") (pinfunction "40_40") (pintype "passive"))
      (node (ref "U3") (pin "57") (pinfunction "PD10/DFSDM_CKOUT/SAI3_FS_B/USART3_CK/FDCAN2_TXFD_MODE/FMC_D15/FMC_DA15/LCD_B3/EVENTOUT_57") (pintype "bidirectional"))
    )
    (net (code "62") (name "/PD11") (class "Default")
      (node (ref "J1") (pin "39") (pinfunction "39_39") (pintype "passive"))
      (node (ref "U3") (pin "58") (pinfunction "PD11/LPTIM2_IN2/I2C4_SMBA/USART3_CTS_NSS/QUADSPI_BK1_IO0/SAI2_SD_A/FMC_A16/EVENTOUT_58") (pintype "bidirectional"))
    )
    (net (code "63") (name "/PD12") (class "Default")
      (node (ref "J1") (pin "38") (pinfunction "38_38") (pintype "passive"))
      (node (ref "U3") (pin "59") (pinfunction "PD12/LPTIM1_IN1/TIM4_CH1/LPTIM2_IN1/I2C4_SCL/USART3_RTS/QUADSPI_BK1_IO1/SAI2_FS_A/FMC_A17/EVENTOUT_59") (pintype "bidirectional"))
    )
    (net (code "64") (name "/PD13") (class "Default")
      (node (ref "J1") (pin "37") (pinfunction "37_37") (pintype "passive"))
      (node (ref "U3") (pin "60") (pinfunction "PD13/LPTIM1_OUT/TIM4_CH2/I2C4_SDA/QUADSPI_BK1_IO3/SAI2_SCK_A/FMC_A18/EVENTOUT_60") (pintype "bidirectional"))
    )
    (net (code "65") (name "/PD14") (class "Default")
      (node (ref "J1") (pin "36") (pinfunction "36_36") (pintype "passive"))
      (node (ref "U3") (pin "61") (pinfunction "PD14/TIM4_CH3/SAI3_MCLK_B/UART8_CTS/FMC_D0/FMC_DA0/EVENTOUT_61") (pintype "bidirectional"))
    )
    (net (code "66") (name "/PD15") (class "Default")
      (node (ref "J1") (pin "35") (pinfunction "35_35") (pintype "passive"))
      (node (ref "U3") (pin "62") (pinfunction "PD15/TIM4_CH4/SAI3_MCLK_A/UART8_RTS/FMC_D1/FMC_DA1/EVENTOUT_62") (pintype "bidirectional"))
    )
    (net (code "67") (name "/PE0") (class "Default")
      (node (ref "J1") (pin "6") (pinfunction "6_6") (pintype "passive"))
      (node (ref "U3") (pin "97") (pinfunction "PE0/LPTIM1_ETR/TIM4_ETR/HRTIM_SCIN/LPTIM2_ETR/UART8_RX/FDCAN1_RXFD_MODE/SAI2_MCK_A/FMC_NBL0/DCMI_D2/EVENTOUT_97") (pintype "bidirectional"))
    )
    (net (code "68") (name "/PE1") (class "Default")
      (node (ref "J1") (pin "5") (pinfunction "5_5") (pintype "passive"))
      (node (ref "U3") (pin "98") (pinfunction "PE1/LPTIM1_IN2/HRTIM_SCOUT/UART8_TX/FDCAN1_TXFD_MODE/FMC_NBL1/DCMI_D3/EVENTOUT_98") (pintype "bidirectional"))
    )
    (net (code "69") (name "/PE2") (class "Default")
      (node (ref "J2") (pin "5") (pinfunction "5_5") (pintype "passive"))
      (node (ref "U3") (pin "1") (pinfunction "PE2/TRACECLK/SAI1_CK1/SPI4_SCK/SAI1_MCLK_A/SAI4_MCLK_A/QUADSPI_BK1_IO2/SAI4_CK1/ETH_MII_TXD3/FMC_A23/EVENTOUT_1") (pintype "bidirectional"))
      (node (ref "microSD Module1") (pin "5") (pinfunction "5_5") (pintype "passive"))
    )
    (net (code "70") (name "/PE3") (class "Default")
      (node (ref "J2") (pin "6") (pinfunction "6_6") (pintype "passive"))
      (node (ref "R_CS_mSD1") (pin "1") (pinfunction "1_1") (pintype "passive"))
      (node (ref "U3") (pin "2") (pinfunction "PE3/TRACED0/TIM15_BKIN/SAI1_SD_B/SAI4_SD_B/FMC_A19/EVENTOUT_2") (pintype "bidirectional"))
    )
    (net (code "71") (name "/PE4") (class "Default")
      (node (ref "J2") (pin "7") (pinfunction "7_7") (pintype "passive"))
      (node (ref "U3") (pin "3") (pinfunction "PE4/TRACED1/SAI1_D2/DFSDM_DATIN3/TIM15_CH1N/SPI4_NSS/SAI1_FS_A/SAI4_FS_A/SAI4_D2/FMC_A20/DCMI_D4/LCD_B0/EVENTOUT_3") (pintype "bidirectional"))
    )
    (net (code "72") (name "/PE5") (class "Default")
      (node (ref "J2") (pin "8") (pinfunction "8_8") (pintype "passive"))
      (node (ref "U3") (pin "4") (pinfunction "PE5/TRACED2/SAI1_CK2/DFSDM_CKIN3/TIM15_CH1/SPI4_MISO/SAI1_SCK_A/SAI4_SCK_A/SAI4_CK2/FMC_A21/DCMI_D6/LCD_G0/EVENTOUT_4") (pintype "bidirectional"))
      (node (ref "microSD Module1") (pin "3") (pinfunction "3_3") (pintype "passive"))
    )
    (net (code "73") (name "/PE6") (class "Default")
      (node (ref "J2") (pin "9") (pinfunction "9_9") (pintype "passive"))
      (node (ref "U3") (pin "5") (pinfunction "PE6/TRACED3/TIM1_BKIN2/SAI1_D1/TIM15_CH2/SPI4_MOSI/SAI1_SD_A/SAI4_SD_A/SAI4_D1/SAI2_MCK_B/TIM1_BKIN2_COMP12/FMC_A22/DCMI_D7/LCD_G1/EVENTOUT_5") (pintype "bidirectional"))
      (node (ref "microSD Module1") (pin "4") (pinfunction "4_4") (pintype "passive"))
    )
    (net (code "74") (name "/PE7") (class "Default")
      (node (ref "J2") (pin "28") (pinfunction "28_28") (pintype "passive"))
      (node (ref "U3") (pin "37") (pinfunction "PE7/TIM1_ETR/DFSDM_DATIN2/UART7_RX/QUADSPI_BK2_IO0/FMC_D4/FMC_DA4/EVENTOUT/OPAMP2_VOUT/COMP_2_INM_37") (pintype "bidirectional"))
    )
    (net (code "75") (name "/PE8") (class "Default")
      (node (ref "J2") (pin "29") (pinfunction "29_29") (pintype "passive"))
      (node (ref "U3") (pin "38") (pinfunction "PE8/TIM1_CH1N/DFSDM_CKIN2/UART7_TX/QUADSPI_BK2_IO1/FMC_D5/FMC_DA5/COMP_2_OUT/EVENTOUT/OPAMP2_VINM_38") (pintype "bidirectional"))
    )
    (net (code "76") (name "/PE9") (class "Default")
      (node (ref "J2") (pin "30") (pinfunction "30_30") (pintype "passive"))
      (node (ref "U3") (pin "39") (pinfunction "PE9/TIM1_CH1/DFSDM_CKOUT/UART7_RTS/QUADSPI_BK2_IO2/FMC_D6/FMC_DA6/EVENTOUT/OPAMP2_VINP/COMP_2_INP_39") (pintype "bidirectional"))
    )
    (net (code "77") (name "/PE10") (class "Default")
      (node (ref "J2") (pin "31") (pinfunction "31_31") (pintype "passive"))
      (node (ref "U3") (pin "40") (pinfunction "PE10/TIM1_CH2N/DFSDM_DATIN4/UART7_CTS/QUADSPI_BK2_IO3/FMC_D7/FMC_DA7/EVENTOUT/COMP_2_INM_40") (pintype "bidirectional"))
    )
    (net (code "78") (name "/PE11") (class "Default")
      (node (ref "J2") (pin "32") (pinfunction "32_32") (pintype "passive"))
      (node (ref "U3") (pin "41") (pinfunction "PE11/TIM1_CH2/DFSDM_CKIN4/SPI4_NSS/SAI2_SD_B/FMC_D8/FMC_DA8/LCD_G3/EVENTOUT/COMP_2_INP_41") (pintype "bidirectional"))
    )
    (net (code "79") (name "/PE12") (class "Default")
      (node (ref "J2") (pin "33") (pinfunction "33_33") (pintype "passive"))
      (node (ref "U3") (pin "42") (pinfunction "PE12/TIM1_CH3N/DFSDM_DATIN5/SPI4_SCK/SAI2_SCK_B/FMC_D9/FMC_DA9/COMP_1_OUT/LCD_B4/EVENTOUT_42") (pintype "bidirectional"))
    )
    (net (code "80") (name "/PE13") (class "Default")
      (node (ref "J2") (pin "34") (pinfunction "34_34") (pintype "passive"))
      (node (ref "U3") (pin "43") (pinfunction "PE13/TIM1_CH3/DFSDM_CKIN5/SPI4_MISO/SAI2_FS_B/FMC_D10/FMC_DA10/COMP_2_OUT/LCD_DE/EVENTOUT_43") (pintype "bidirectional"))
    )
    (net (code "81") (name "/PE14") (class "Default")
      (node (ref "J2") (pin "35") (pinfunction "35_35") (pintype "passive"))
      (node (ref "U3") (pin "44") (pinfunction "PE14/TIM1_CH4/SPI4_MOSI/SAI2_MCK_B/FMC_D11/FMC_DA11/LCD_CLK/EVENTOUT_44") (pintype "bidirectional"))
    )
    (net (code "82") (name "/PE15") (class "Default")
      (node (ref "J2") (pin "36") (pinfunction "36_36") (pintype "passive"))
      (node (ref "U3") (pin "45") (pinfunction "PE15/TIM1_BKIN/HDMI__TIM1_BKIN/FMC_D12/FMC_DA12/TIM1_BKIN_COMP12/LCD_R7/EVENTOUT_45") (pintype "bidirectional"))
    )
    (net (code "83") (name "/SWCLK") (class "Default")
      (node (ref "PROGRAM1") (pin "2") (pinfunction "2_2") (pintype "passive"))
      (node (ref "R11") (pin "1") (pinfunction "1_1") (pintype "passive"))
      (node (ref "U3") (pin "76") (pinfunction "PA14/JTCK-SWCLK/EVENTOUT_76") (pintype "bidirectional"))
    )
    (net (code "84") (name "/SWDIO") (class "Default")
      (node (ref "PROGRAM1") (pin "3") (pinfunction "3_3") (pintype "passive"))
      (node (ref "R10") (pin "1") (pinfunction "1_1") (pintype "passive"))
      (node (ref "U3") (pin "72") (pinfunction "PA13/JTMS-SWDIO/EVENTOUT_72") (pintype "bidirectional"))
    )
    (net (code "85") (name "/VCAP1") (class "Default")
      (node (ref "C13") (pin "1") (pinfunction "1_1") (pintype "passive"))
      (node (ref "U3") (pin "48") (pinfunction "VCAP_48") (pintype "power_in"))
    )
    (net (code "86") (name "/VCAP2") (class "Default")
      (node (ref "C19") (pin "1") (pinfunction "1_1") (pintype "passive"))
      (node (ref "U3") (pin "73") (pinfunction "VCAP_73") (pintype "power_in"))
    )
    (net (code "87") (name "3V3") (class "Default")
      (node (ref "C21") (pin "1") (pinfunction "1_1") (pintype "passive"))
      (node (ref "C22") (pin "1") (pinfunction "1_1") (pintype "passive"))
      (node (ref "C23") (pin "1") (pinfunction "1_1") (pintype "passive"))
      (node (ref "C24") (pin "1") (pinfunction "1_1") (pintype "passive"))
      (node (ref "C25") (pin "1") (pinfunction "1_1") (pintype "passive"))
      (node (ref "C26") (pin "1") (pinfunction "1_1") (pintype "passive"))
      (node (ref "Ferrite bead1") (pin "1") (pinfunction "1_1") (pintype "passive"))
      (node (ref "J1") (pin "3") (pinfunction "3_3") (pintype "passive"))
      (node (ref "J1") (pin "49") (pinfunction "49_49") (pintype "passive"))
      (node (ref "J2") (pin "3") (pinfunction "3_3") (pintype "passive"))
      (node (ref "J2") (pin "41") (pinfunction "41_41") (pintype "passive"))
      (node (ref "L2") (pin "1") (pinfunction "1_1") (pintype "passive"))
      (node (ref "PROGRAM1") (pin "5") (pinfunction "5_5") (pintype "passive"))
      (node (ref "R10") (pin "2") (pinfunction "2_2") (pintype "passive"))
      (node (ref "R11") (pin "2") (pinfunction "2_2") (pintype "passive"))
      (node (ref "R8") (pin "2") (pinfunction "2_2") (pintype "passive"))
      (node (ref "U3") (pin "100") (pinfunction "VDD_100") (pintype "power_in"))
      (node (ref "U3") (pin "11") (pinfunction "VDD_11") (pintype "power_in"))
      (node (ref "U3") (pin "27") (pinfunction "VDD_27") (pintype "power_in"))
      (node (ref "U3") (pin "50") (pinfunction "VDD_50") (pintype "power_in"))
      (node (ref "U3") (pin "75") (pinfunction "VDD_75") (pintype "power_in"))
    )
    (net (code "88") (name "5_SW") (class "Default")
      (node (ref "J1") (pin "1") (pinfunction "1_1") (pintype "passive"))
      (node (ref "J1") (pin "47") (pinfunction "47_47") (pintype "passive"))
      (node (ref "J2") (pin "1") (pinfunction "1_1") (pintype "passive"))
      (node (ref "J2") (pin "39") (pinfunction "39_39") (pintype "passive"))
      (node (ref "microSD Module1") (pin "2") (pinfunction "2_2") (pintype "passive"))
    )
    (net (code "89") (name "GND") (class "Default")
      (node (ref "BT1") (pin "N") (pinfunction "NEG_N") (pintype "passive"))
      (node (ref "C11") (pin "1") (pinfunction "1_1") (pintype "passive"))
      (node (ref "C12") (pin "1") (pinfunction "1_1") (pintype "passive"))
      (node (ref "C13") (pin "2") (pinfunction "2_2") (pintype "passive"))
      (node (ref "C18") (pin "1") (pinfunction "1_1") (pintype "passive"))
      (node (ref "C19") (pin "2") (pinfunction "2_2") (pintype "passive"))
      (node (ref "C20") (pin "1") (pinfunction "1_1") (pintype "passive"))
      (node (ref "C21") (pin "2") (pinfunction "2_2") (pintype "passive"))
      (node (ref "C22") (pin "2") (pinfunction "2_2") (pintype "passive"))
      (node (ref "C23") (pin "2") (pinfunction "2_2") (pintype "passive"))
      (node (ref "C24") (pin "2") (pinfunction "2_2") (pintype "passive"))
      (node (ref "C25") (pin "2") (pinfunction "2_2") (pintype "passive"))
      (node (ref "C26") (pin "2") (pinfunction "2_2") (pintype "passive"))
      (node (ref "C28") (pin "2") (pinfunction "2_2") (pintype "passive"))
      (node (ref "Ferrite bead2") (pin "1") (pinfunction "1_1") (pintype "passive"))
      (node (ref "J1") (pin "2") (pinfunction "2_2") (pintype "passive"))
      (node (ref "J1") (pin "4") (pinfunction "4_4") (pintype "passive"))
      (node (ref "J1") (pin "48") (pinfunction "48_48") (pintype "passive"))
      (node (ref "J1") (pin "50") (pinfunction "50_50") (pintype "passive"))
      (node (ref "J2") (pin "2") (pinfunction "2_2") (pintype "passive"))
      (node (ref "J2") (pin "4") (pinfunction "4_4") (pintype "passive"))
      (node (ref "J2") (pin "40") (pinfunction "40_40") (pintype "passive"))
      (node (ref "J2") (pin "42") (pinfunction "42_42") (pintype "passive"))
      (node (ref "PROGRAM1") (pin "1") (pinfunction "1_1") (pintype "passive"))
      (node (ref "R13") (pin "1") (pinfunction "1_1") (pintype "passive"))
      (node (ref "R14") (pin "1") (pinfunction "1_1") (pintype "passive"))
      (node (ref "R15") (pin "1") (pinfunction "1_1") (pintype "passive"))
      (node (ref "R16") (pin "1") (pinfunction "1_1") (pintype "passive"))
      (node (ref "R9") (pin "2") (pinfunction "2_2") (pintype "passive"))
      (node (ref "S1") (pin "2") (pinfunction "2_2") (pintype "passive"))
      (node (ref "U3") (pin "10") (pinfunction "VSS_10") (pintype "power_in"))
      (node (ref "U3") (pin "26") (pinfunction "VSS_26") (pintype "power_in"))
      (node (ref "U3") (pin "49") (pinfunction "VSS_49") (pintype "power_in"))
      (node (ref "U3") (pin "74") (pinfunction "VSS_74") (pintype "power_in"))
      (node (ref "U3") (pin "99") (pinfunction "VSS_99") (pintype "power_in"))
      (node (ref "microSD Module1") (pin "1") (pinfunction "1_1") (pintype "passive"))
    )
    (net (code "90") (name "Net-(BT1-POS)") (class "Default")
      (node (ref "BT1") (pin "P") (pinfunction "POS_P") (pintype "passive"))
      (node (ref "U3") (pin "6") (pinfunction "VBAT_6") (pintype "power_in"))
    )
    (net (code "91") (name "Net-(PWM_LED1-Pad1)") (class "Default")
      (node (ref "PWM_LED1") (pin "1") (pinfunction "1_1") (pintype "passive"))
      (node (ref "R_PWM1") (pin "2") (pinfunction "2_2") (pintype "passive"))
    )
    (net (code "92") (name "Net-(PWM_LED1-Pad2)") (class "Default")
      (node (ref "PWM_LED1") (pin "2") (pinfunction "2_2") (pintype "passive"))
      (node (ref "R13") (pin "2") (pinfunction "2_2") (pintype "passive"))
    )
    (net (code "93") (name "Net-(PWM_LED2-Pad1)") (class "Default")
      (node (ref "PWM_LED2") (pin "1") (pinfunction "1_1") (pintype "passive"))
      (node (ref "R_PWM2") (pin "2") (pinfunction "2_2") (pintype "passive"))
    )
    (net (code "94") (name "Net-(PWM_LED2-Pad2)") (class "Default")
      (node (ref "PWM_LED2") (pin "2") (pinfunction "2_2") (pintype "passive"))
      (node (ref "R14") (pin "2") (pinfunction "2_2") (pintype "passive"))
    )
    (net (code "95") (name "Net-(PWM_LED3-Pad1)") (class "Default")
      (node (ref "PWM_LED3") (pin "1") (pinfunction "1_1") (pintype "passive"))
      (node (ref "R_PWM3") (pin "2") (pinfunction "2_2") (pintype "passive"))
    )
    (net (code "96") (name "Net-(PWM_LED3-Pad2)") (class "Default")
      (node (ref "PWM_LED3") (pin "2") (pinfunction "2_2") (pintype "passive"))
      (node (ref "R15") (pin "2") (pinfunction "2_2") (pintype "passive"))
    )
    (net (code "97") (name "Net-(PWM_LED4-Pad1)") (class "Default")
      (node (ref "PWM_LED4") (pin "1") (pinfunction "1_1") (pintype "passive"))
      (node (ref "R_PWM4") (pin "2") (pinfunction "2_2") (pintype "passive"))
    )
    (net (code "98") (name "Net-(PWM_LED4-Pad2)") (class "Default")
      (node (ref "PWM_LED4") (pin "2") (pinfunction "2_2") (pintype "passive"))
      (node (ref "R16") (pin "2") (pinfunction "2_2") (pintype "passive"))
    )
    (net (code "99") (name "Net-(R_CS_mSD1-Pad2)") (class "Default")
      (node (ref "R_CS_mSD1") (pin "2") (pinfunction "2_2") (pintype "passive"))
      (node (ref "microSD Module1") (pin "6") (pinfunction "6_6") (pintype "passive"))
    )
    (net (code "100") (name "VDDA") (class "Default")
      (node (ref "C14") (pin "1") (pinfunction "1_1") (pintype "passive"))
      (node (ref "C15") (pin "1") (pinfunction "1_1") (pintype "passive"))
      (node (ref "C27") (pin "1") (pinfunction "1_1") (pintype "passive"))
      (node (ref "C29") (pin "1") (pinfunction "1_1") (pintype "passive"))
      (node (ref "Ferrite bead1") (pin "2") (pinfunction "2_2") (pintype "passive"))
      (node (ref "L2") (pin "2") (pinfunction "2_2") (pintype "passive"))
      (node (ref "R12") (pin "2") (pinfunction "2_2") (pintype "passive"))
      (node (ref "U3") (pin "21") (pinfunction "VDDA_21") (pintype "power_in"))
    )
    (net (code "101") (name "VREF+") (class "Default")
      (node (ref "C16") (pin "1") (pinfunction "1_1") (pintype "passive"))
      (node (ref "C17") (pin "1") (pinfunction "1_1") (pintype "passive"))
      (node (ref "R12") (pin "1") (pinfunction "1_1") (pintype "passive"))
      (node (ref "U3") (pin "20") (pinfunction "VREF+_20") (pintype "power_in"))
    )
    (net (code "102") (name "VSSA") (class "Default")
      (node (ref "C14") (pin "2") (pinfunction "2_2") (pintype "passive"))
      (node (ref "C15") (pin "2") (pinfunction "2_2") (pintype "passive"))
      (node (ref "C16") (pin "2") (pinfunction "2_2") (pintype "passive"))
      (node (ref "C17") (pin "2") (pinfunction "2_2") (pintype "passive"))
      (node (ref "C27") (pin "2") (pinfunction "2_2") (pintype "passive"))
      (node (ref "C29") (pin "2") (pinfunction "2_2") (pintype "passive"))
      (node (ref "Ferrite bead2") (pin "2") (pinfunction "2_2") (pintype "passive"))
      (node (ref "U3") (pin "19") (pinfunction "VSSA_19") (pintype "power_in"))
    )
    (net (code "103") (name "unconnected-(J1-Pad51)") (class "Default")
      (node (ref "J1") (pin "51") (pinfunction "51_51") (pintype "passive+no_connect"))
    )
    (net (code "104") (name "unconnected-(J1-Pad52)") (class "Default")
      (node (ref "J1") (pin "52") (pinfunction "52_52") (pintype "passive+no_connect"))
    )
    (net (code "105") (name "unconnected-(J1-Pad53)") (class "Default")
      (node (ref "J1") (pin "53") (pinfunction "53_53") (pintype "passive+no_connect"))
    )
    (net (code "106") (name "unconnected-(J1-Pad54)") (class "Default")
      (node (ref "J1") (pin "54") (pinfunction "54_54") (pintype "passive+no_connect"))
    )
    (net (code "107") (name "unconnected-(J1-Pad55)") (class "Default")
      (node (ref "J1") (pin "55") (pinfunction "55_55") (pintype "passive+no_connect"))
    )
    (net (code "108") (name "unconnected-(J1-Pad56)") (class "Default")
      (node (ref "J1") (pin "56") (pinfunction "56_56") (pintype "passive+no_connect"))
    )
    (net (code "109") (name "unconnected-(J1-Pad57)") (class "Default")
      (node (ref "J1") (pin "57") (pinfunction "57_57") (pintype "passive+no_connect"))
    )
    (net (code "110") (name "unconnected-(J1-Pad58)") (class "Default")
      (node (ref "J1") (pin "58") (pinfunction "58_58") (pintype "passive+no_connect"))
    )
    (net (code "111") (name "unconnected-(J1-Pad59)") (class "Default")
      (node (ref "J1") (pin "59") (pinfunction "59_59") (pintype "passive+no_connect"))
    )
    (net (code "112") (name "unconnected-(J1-Pad60)") (class "Default")
      (node (ref "J1") (pin "60") (pinfunction "60_60") (pintype "passive+no_connect"))
    )
    (net (code "113") (name "unconnected-(J1-Pad61)") (class "Default")
      (node (ref "J1") (pin "61") (pinfunction "61_61") (pintype "passive+no_connect"))
    )
    (net (code "114") (name "unconnected-(J1-Pad62)") (class "Default")
      (node (ref "J1") (pin "62") (pinfunction "62_62") (pintype "passive+no_connect"))
    )
    (net (code "115") (name "unconnected-(J1-Pad63)") (class "Default")
      (node (ref "J1") (pin "63") (pinfunction "63_63") (pintype "passive+no_connect"))
    )
    (net (code "116") (name "unconnected-(J1-Pad64)") (class "Default")
      (node (ref "J1") (pin "64") (pinfunction "64_64") (pintype "passive+no_connect"))
    )
    (net (code "117") (name "unconnected-(J2-Pad43)") (class "Default")
      (node (ref "J2") (pin "43") (pinfunction "43_43") (pintype "passive+no_connect"))
    )
    (net (code "118") (name "unconnected-(J2-Pad44)") (class "Default")
      (node (ref "J2") (pin "44") (pinfunction "44_44") (pintype "passive+no_connect"))
    )
    (net (code "119") (name "unconnected-(J2-Pad45)") (class "Default")
      (node (ref "J2") (pin "45") (pinfunction "45_45") (pintype "passive+no_connect"))
    )
    (net (code "120") (name "unconnected-(J2-Pad46)") (class "Default")
      (node (ref "J2") (pin "46") (pinfunction "46_46") (pintype "passive+no_connect"))
    )
    (net (code "121") (name "unconnected-(J2-Pad47)") (class "Default")
      (node (ref "J2") (pin "47") (pinfunction "47_47") (pintype "passive+no_connect"))
    )
    (net (code "122") (name "unconnected-(J2-Pad48)") (class "Default")
      (node (ref "J2") (pin "48") (pinfunction "48_48") (pintype "passive+no_connect"))
    )
    (net (code "123") (name "unconnected-(J2-Pad49)") (class "Default")
      (node (ref "J2") (pin "49") (pinfunction "49_49") (pintype "passive+no_connect"))
    )
    (net (code "124") (name "unconnected-(J2-Pad50)") (class "Default")
      (node (ref "J2") (pin "50") (pinfunction "50_50") (pintype "passive+no_connect"))
    )
    (net (code "125") (name "unconnected-(J2-Pad51)") (class "Default")
      (node (ref "J2") (pin "51") (pinfunction "51_51") (pintype "passive+no_connect"))
    )
    (net (code "126") (name "unconnected-(J2-Pad52)") (class "Default")
      (node (ref "J2") (pin "52") (pinfunction "52_52") (pintype "passive+no_connect"))
    )
    (net (code "127") (name "unconnected-(J2-Pad53)") (class "Default")
      (node (ref "J2") (pin "53") (pinfunction "53_53") (pintype "passive+no_connect"))
    )
    (net (code "128") (name "unconnected-(J2-Pad54)") (class "Default")
      (node (ref "J2") (pin "54") (pinfunction "54_54") (pintype "passive+no_connect"))
    )
    (net (code "129") (name "unconnected-(J2-Pad55)") (class "Default")
      (node (ref "J2") (pin "55") (pinfunction "55_55") (pintype "passive+no_connect"))
    )
    (net (code "130") (name "unconnected-(J2-Pad56)") (class "Default")
      (node (ref "J2") (pin "56") (pinfunction "56_56") (pintype "passive+no_connect"))
    )
    (net (code "131") (name "unconnected-(J2-Pad57)") (class "Default")
      (node (ref "J2") (pin "57") (pinfunction "57_57") (pintype "passive+no_connect"))
    )
    (net (code "132") (name "unconnected-(J2-Pad58)") (class "Default")
      (node (ref "J2") (pin "58") (pinfunction "58_58") (pintype "passive+no_connect"))
    )
    (net (code "133") (name "unconnected-(J2-Pad59)") (class "Default")
      (node (ref "J2") (pin "59") (pinfunction "59_59") (pintype "passive+no_connect"))
    )
    (net (code "134") (name "unconnected-(J2-Pad60)") (class "Default")
      (node (ref "J2") (pin "60") (pinfunction "60_60") (pintype "passive+no_connect"))
    )
    (net (code "135") (name "unconnected-(J2-Pad61)") (class "Default")
      (node (ref "J2") (pin "61") (pinfunction "61_61") (pintype "passive+no_connect"))
    )
    (net (code "136") (name "unconnected-(J2-Pad62)") (class "Default")
      (node (ref "J2") (pin "62") (pinfunction "62_62") (pintype "passive+no_connect"))
    )
    (net (code "137") (name "unconnected-(J2-Pad63)") (class "Default")
      (node (ref "J2") (pin "63") (pinfunction "63_63") (pintype "passive+no_connect"))
    )
    (net (code "138") (name "unconnected-(J2-Pad64)") (class "Default")
      (node (ref "J2") (pin "64") (pinfunction "64_64") (pintype "passive+no_connect"))
    )
    (net (code "139") (name "unconnected-(Y2-Pad1)") (class "Default")
      (node (ref "Y2") (pin "1") (pinfunction "1_1") (pintype "passive"))
    )
    (net (code "140") (name "unconnected-(Y2-Pad3)") (class "Default")
      (node (ref "Y2") (pin "3") (pinfunction "3_3") (pintype "passive"))
    )
  )
)
